# small_line.net
KiCad netlist of a schematic drawn in EAGLE
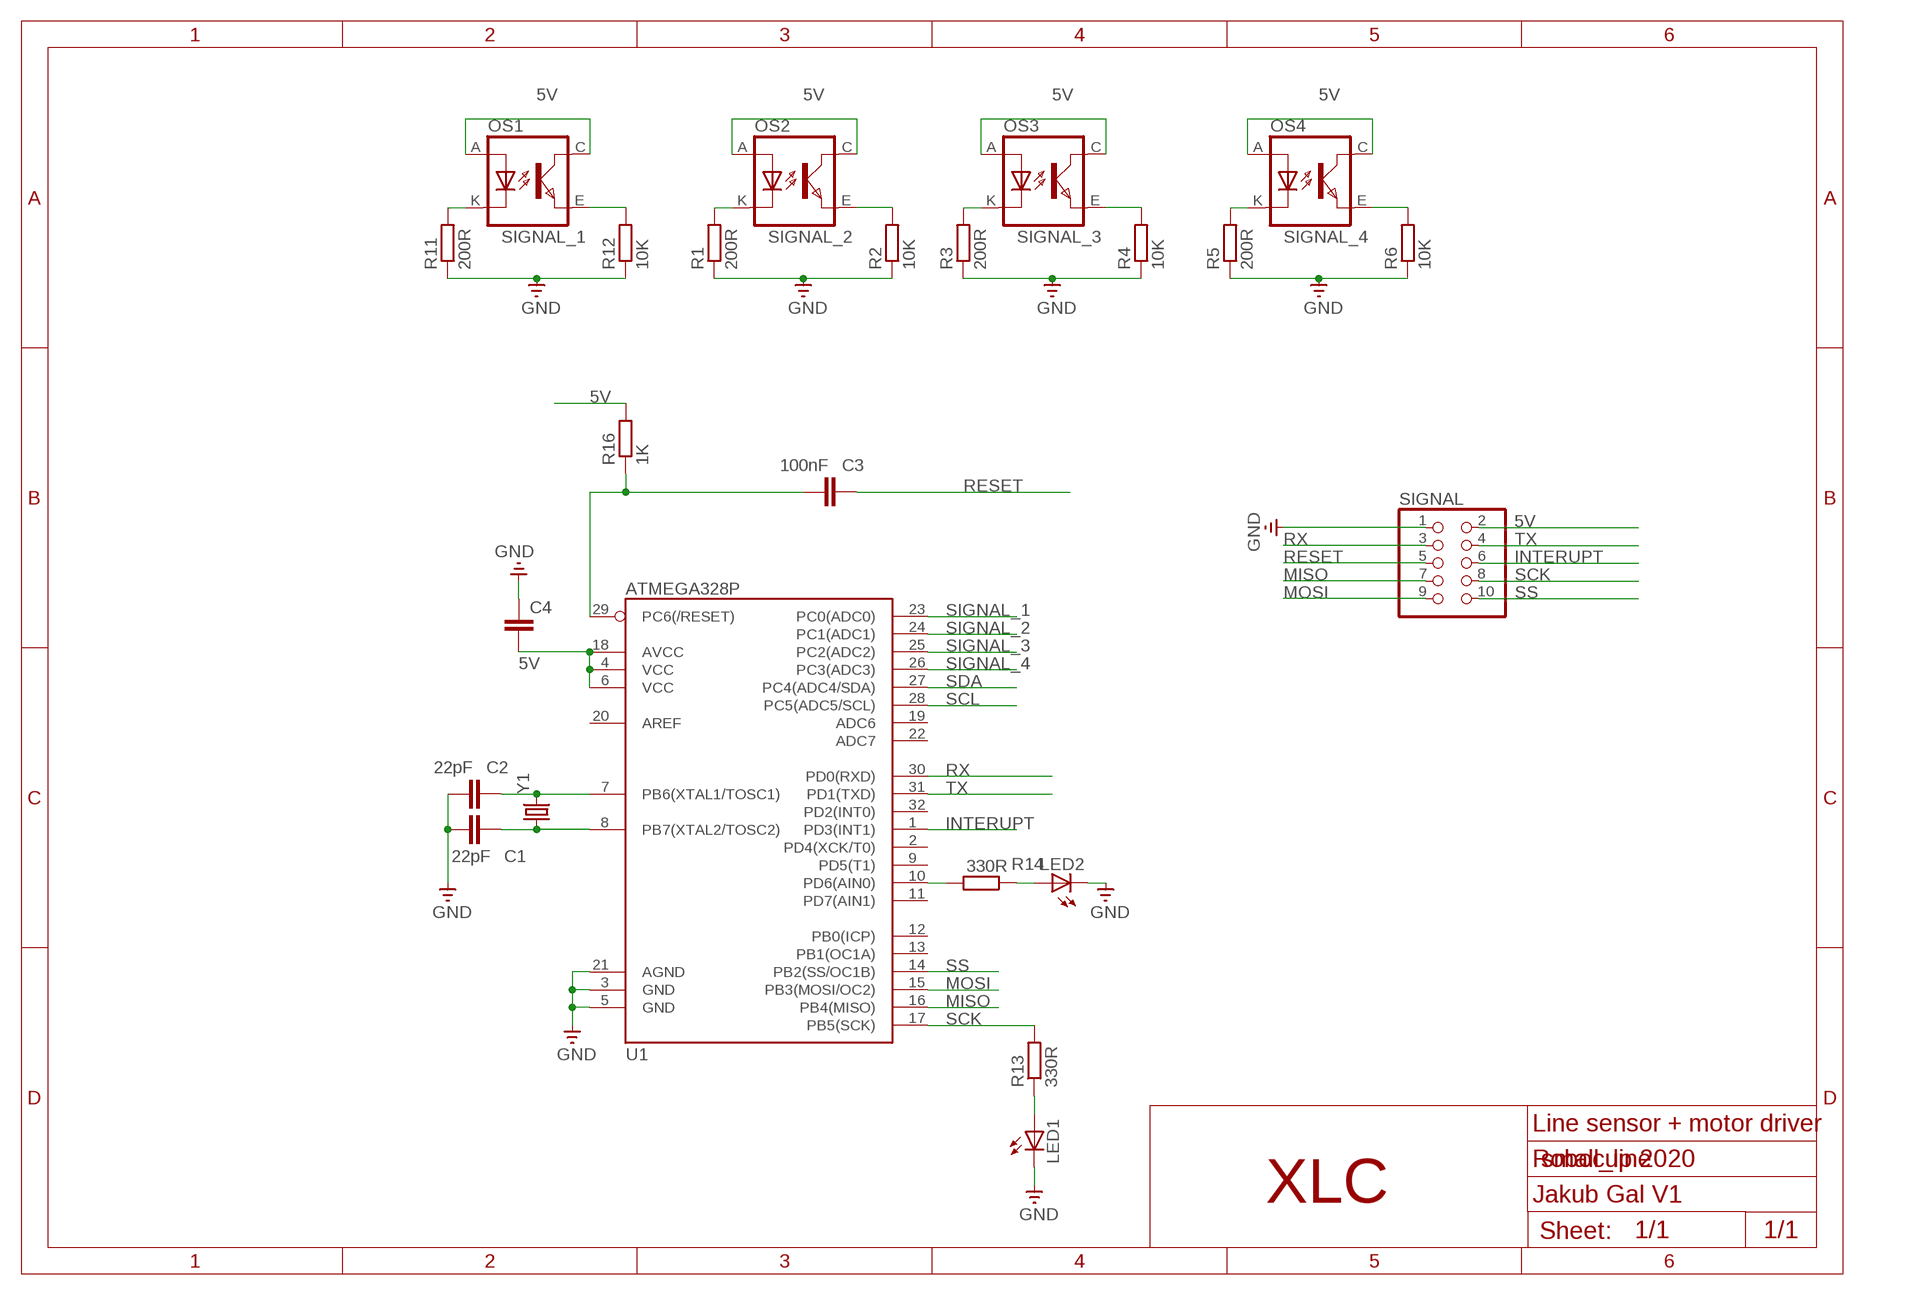
[diagram p0: schematic, sheet 1]

(export (version "E")
  (design (tool "Eeschema 10.0.6"))
  (components
    (comp (ref "C1")
      (value "22pF")
      (footprint "eagle-import:C0603")
      (libsource (lib "eagle-import") (part "C-EUC0603"))
    )
    (comp (ref "C2")
      (value "22pF")
      (footprint "eagle-import:C0603")
      (libsource (lib "eagle-import") (part "C-EUC0603"))
    )
    (comp (ref "C3")
      (value "100nF")
      (footprint "eagle-import:C0603")
      (libsource (lib "eagle-import") (part "C-EUC0603"))
    )
    (comp (ref "C4")
      (value "C-EUC0603")
      (footprint "eagle-import:C0603")
      (libsource (lib "eagle-import") (part "rcl_334_C-EUC0603"))
    )
    (comp (ref "LED1")
      (value "LEDCHIPLED_0603")
      (footprint "eagle-import:CHIPLED_0603")
      (libsource (lib "eagle-import") (part "LEDCHIPLED_0603"))
    )
    (comp (ref "LED2")
      (value "LEDCHIPLED_0603")
      (footprint "eagle-import:CHIPLED_0603")
      (libsource (lib "eagle-import") (part "LEDCHIPLED_0603"))
    )
    (comp (ref "OS1")
      (value "TCRT5000")
      (footprint "eagle-import:TCRT5000")
      (libsource (lib "eagle-import") (part "TCRT5000"))
    )
    (comp (ref "OS2")
      (value "TCRT5000")
      (footprint "eagle-import:TCRT5000")
      (libsource (lib "eagle-import") (part "TCRT5000"))
    )
    (comp (ref "OS3")
      (value "TCRT5000")
      (footprint "eagle-import:TCRT5000")
      (libsource (lib "eagle-import") (part "TCRT5000"))
    )
    (comp (ref "OS4")
      (value "TCRT5000")
      (footprint "eagle-import:TCRT5000")
      (libsource (lib "eagle-import") (part "TCRT5000"))
    )
    (comp (ref "R1")
      (value "200R")
      (footprint "eagle-import:R0603")
      (libsource (lib "eagle-import") (part "R-EU_R0603"))
    )
    (comp (ref "R2")
      (value "10K")
      (footprint "eagle-import:R0603")
      (libsource (lib "eagle-import") (part "R-EU_R0603"))
    )
    (comp (ref "R3")
      (value "200R")
      (footprint "eagle-import:R0603")
      (libsource (lib "eagle-import") (part "R-EU_R0603"))
    )
    (comp (ref "R4")
      (value "10K")
      (footprint "eagle-import:R0603")
      (libsource (lib "eagle-import") (part "R-EU_R0603"))
    )
    (comp (ref "R5")
      (value "200R")
      (footprint "eagle-import:R0603")
      (libsource (lib "eagle-import") (part "R-EU_R0603"))
    )
    (comp (ref "R6")
      (value "10K")
      (footprint "eagle-import:R0603")
      (libsource (lib "eagle-import") (part "R-EU_R0603"))
    )
    (comp (ref "R11")
      (value "200R")
      (footprint "eagle-import:R0603")
      (libsource (lib "eagle-import") (part "R-EU_R0603"))
    )
    (comp (ref "R12")
      (value "10K")
      (footprint "eagle-import:R0603")
      (libsource (lib "eagle-import") (part "R-EU_R0603"))
    )
    (comp (ref "R13")
      (value "330R")
      (footprint "eagle-import:R0603")
      (libsource (lib "eagle-import") (part "R-EU_R0603"))
    )
    (comp (ref "R14")
      (value "330R")
      (footprint "eagle-import:R0603")
      (libsource (lib "eagle-import") (part "R-EU_R0603"))
    )
    (comp (ref "R16")
      (value "1K")
      (footprint "eagle-import:R0603")
      (libsource (lib "eagle-import") (part "R-EU_R0603"))
    )
    (comp (ref "SIGNAL")
      (value "PINHD-2X5IDC")
      (footprint "eagle-import:2X05_IDC")
      (libsource (lib "eagle-import") (part "PINHD-2X5IDC"))
    )
    (comp (ref "U1")
      (value "ATMEGA328P")
      (footprint "eagle-import:TQFP32-08")
      (libsource (lib "eagle-import") (part "ATMEGA328_SMT"))
    )
    (comp (ref "Y1")
      (value "CRYSTALHC49US")
      (footprint "eagle-import:HC49US")
      (libsource (lib "eagle-import") (part "CRYSTALHC49US"))
    )
  )
  (nets
    (net (code "1") (name "/5V") (class "Default")
      (node (ref "C4") (pin "2") (pinfunction "2_2") (pintype "passive"))
      (node (ref "OS1") (pin "A") (pinfunction "ANODE_A") (pintype "passive"))
      (node (ref "OS1") (pin "C") (pinfunction "COLLECTOR_C") (pintype "passive"))
      (node (ref "OS2") (pin "A") (pinfunction "ANODE_A") (pintype "passive"))
      (node (ref "OS2") (pin "C") (pinfunction "COLLECTOR_C") (pintype "passive"))
      (node (ref "OS3") (pin "A") (pinfunction "ANODE_A") (pintype "passive"))
      (node (ref "OS3") (pin "C") (pinfunction "COLLECTOR_C") (pintype "passive"))
      (node (ref "OS4") (pin "A") (pinfunction "ANODE_A") (pintype "passive"))
      (node (ref "OS4") (pin "C") (pinfunction "COLLECTOR_C") (pintype "passive"))
      (node (ref "R16") (pin "2") (pinfunction "2_2") (pintype "passive"))
      (node (ref "SIGNAL") (pin "2") (pinfunction "2_2") (pintype "passive"))
      (node (ref "U1") (pin "18") (pinfunction "AVCC_18") (pintype "bidirectional"))
      (node (ref "U1") (pin "4") (pinfunction "VCC_4") (pintype "bidirectional"))
      (node (ref "U1") (pin "6") (pinfunction "VCC_6") (pintype "bidirectional"))
    )
    (net (code "2") (name "/INTERUPT") (class "Default")
      (node (ref "SIGNAL") (pin "6") (pinfunction "6_6") (pintype "passive"))
      (node (ref "U1") (pin "1") (pinfunction "PD3(INT1)_1") (pintype "bidirectional"))
    )
    (net (code "3") (name "/MISO") (class "Default")
      (node (ref "SIGNAL") (pin "7") (pinfunction "7_7") (pintype "passive"))
      (node (ref "U1") (pin "16") (pinfunction "PB4(MISO)_16") (pintype "bidirectional"))
    )
    (net (code "4") (name "/MOSI") (class "Default")
      (node (ref "SIGNAL") (pin "9") (pinfunction "9_9") (pintype "passive"))
      (node (ref "U1") (pin "15") (pinfunction "PB3(MOSI/OC2)_15") (pintype "bidirectional"))
    )
    (net (code "5") (name "/RESET") (class "Default")
      (node (ref "C3") (pin "2") (pinfunction "2_2") (pintype "passive"))
      (node (ref "SIGNAL") (pin "5") (pinfunction "5_5") (pintype "passive"))
    )
    (net (code "6") (name "/RX") (class "Default")
      (node (ref "SIGNAL") (pin "3") (pinfunction "3_3") (pintype "passive"))
      (node (ref "U1") (pin "30") (pinfunction "PD0(RXD)_30") (pintype "bidirectional"))
    )
    (net (code "7") (name "/SCK") (class "Default")
      (node (ref "R13") (pin "2") (pinfunction "2_2") (pintype "passive"))
      (node (ref "SIGNAL") (pin "8") (pinfunction "8_8") (pintype "passive"))
      (node (ref "U1") (pin "17") (pinfunction "PB5(SCK)_17") (pintype "bidirectional"))
    )
    (net (code "8") (name "/SCL") (class "Default")
      (node (ref "U1") (pin "28") (pinfunction "PC5(ADC5/SCL)_28") (pintype "bidirectional"))
    )
    (net (code "9") (name "/SDA") (class "Default")
      (node (ref "U1") (pin "27") (pinfunction "PC4(ADC4/SDA)_27") (pintype "bidirectional"))
    )
    (net (code "10") (name "/SIGNAL_1") (class "Default")
      (node (ref "OS1") (pin "E") (pinfunction "EMITTER_E") (pintype "passive"))
      (node (ref "R12") (pin "2") (pinfunction "2_2") (pintype "passive"))
      (node (ref "U1") (pin "23") (pinfunction "PC0(ADC0)_23") (pintype "bidirectional"))
    )
    (net (code "11") (name "/SIGNAL_2") (class "Default")
      (node (ref "OS2") (pin "E") (pinfunction "EMITTER_E") (pintype "passive"))
      (node (ref "R2") (pin "2") (pinfunction "2_2") (pintype "passive"))
      (node (ref "U1") (pin "24") (pinfunction "PC1(ADC1)_24") (pintype "bidirectional"))
    )
    (net (code "12") (name "/SIGNAL_3") (class "Default")
      (node (ref "OS3") (pin "E") (pinfunction "EMITTER_E") (pintype "passive"))
      (node (ref "R4") (pin "2") (pinfunction "2_2") (pintype "passive"))
      (node (ref "U1") (pin "25") (pinfunction "PC2(ADC2)_25") (pintype "bidirectional"))
    )
    (net (code "13") (name "/SIGNAL_4") (class "Default")
      (node (ref "OS4") (pin "E") (pinfunction "EMITTER_E") (pintype "passive"))
      (node (ref "R6") (pin "2") (pinfunction "2_2") (pintype "passive"))
      (node (ref "U1") (pin "26") (pinfunction "PC3(ADC3)_26") (pintype "bidirectional"))
    )
    (net (code "14") (name "/SS") (class "Default")
      (node (ref "SIGNAL") (pin "10") (pinfunction "10_10") (pintype "passive"))
      (node (ref "U1") (pin "14") (pinfunction "PB2(SS/OC1B)_14") (pintype "bidirectional"))
    )
    (net (code "15") (name "/TX") (class "Default")
      (node (ref "SIGNAL") (pin "4") (pinfunction "4_4") (pintype "passive"))
      (node (ref "U1") (pin "31") (pinfunction "PD1(TXD)_31") (pintype "bidirectional"))
    )
    (net (code "16") (name "GND") (class "Default")
      (node (ref "C1") (pin "1") (pinfunction "1_1") (pintype "passive"))
      (node (ref "C2") (pin "1") (pinfunction "1_1") (pintype "passive"))
      (node (ref "C4") (pin "1") (pinfunction "1_1") (pintype "passive"))
      (node (ref "LED1") (pin "C") (pinfunction "C_C") (pintype "passive"))
      (node (ref "LED2") (pin "C") (pinfunction "C_C") (pintype "passive"))
      (node (ref "R1") (pin "1") (pinfunction "1_1") (pintype "passive"))
      (node (ref "R11") (pin "1") (pinfunction "1_1") (pintype "passive"))
      (node (ref "R12") (pin "1") (pinfunction "1_1") (pintype "passive"))
      (node (ref "R2") (pin "1") (pinfunction "1_1") (pintype "passive"))
      (node (ref "R3") (pin "1") (pinfunction "1_1") (pintype "passive"))
      (node (ref "R4") (pin "1") (pinfunction "1_1") (pintype "passive"))
      (node (ref "R5") (pin "1") (pinfunction "1_1") (pintype "passive"))
      (node (ref "R6") (pin "1") (pinfunction "1_1") (pintype "passive"))
      (node (ref "SIGNAL") (pin "1") (pinfunction "1_1") (pintype "passive"))
      (node (ref "U1") (pin "21") (pinfunction "AGND_21") (pintype "bidirectional"))
      (node (ref "U1") (pin "3") (pinfunction "GND_3") (pintype "bidirectional"))
      (node (ref "U1") (pin "5") (pinfunction "GND_5") (pintype "bidirectional"))
    )
    (net (code "17") (name "Net-(LED1-PadA)") (class "Default")
      (node (ref "LED1") (pin "A") (pinfunction "A_A") (pintype "passive"))
      (node (ref "R13") (pin "1") (pinfunction "1_1") (pintype "passive"))
    )
    (net (code "18") (name "Net-(LED2-PadA)") (class "Default")
      (node (ref "LED2") (pin "A") (pinfunction "A_A") (pintype "passive"))
      (node (ref "R14") (pin "1") (pinfunction "1_1") (pintype "passive"))
    )
    (net (code "19") (name "Net-(OS1-CATHODE)") (class "Default")
      (node (ref "OS1") (pin "K") (pinfunction "CATHODE_K") (pintype "passive"))
      (node (ref "R11") (pin "2") (pinfunction "2_2") (pintype "passive"))
    )
    (net (code "20") (name "Net-(OS2-CATHODE)") (class "Default")
      (node (ref "OS2") (pin "K") (pinfunction "CATHODE_K") (pintype "passive"))
      (node (ref "R1") (pin "2") (pinfunction "2_2") (pintype "passive"))
    )
    (net (code "21") (name "Net-(OS3-CATHODE)") (class "Default")
      (node (ref "OS3") (pin "K") (pinfunction "CATHODE_K") (pintype "passive"))
      (node (ref "R3") (pin "2") (pinfunction "2_2") (pintype "passive"))
    )
    (net (code "22") (name "Net-(OS4-CATHODE)") (class "Default")
      (node (ref "OS4") (pin "K") (pinfunction "CATHODE_K") (pintype "passive"))
      (node (ref "R5") (pin "2") (pinfunction "2_2") (pintype "passive"))
    )
    (net (code "23") (name "Net-(U1-PB6(XTAL1{slash}TOSC1))") (class "Default")
      (node (ref "C2") (pin "2") (pinfunction "2_2") (pintype "passive"))
      (node (ref "U1") (pin "7") (pinfunction "PB6(XTAL1/TOSC1)_7") (pintype "bidirectional"))
      (node (ref "Y1") (pin "2") (pinfunction "2_2") (pintype "passive"))
    )
    (net (code "24") (name "Net-(U1-PB7(XTAL2{slash}TOSC2))") (class "Default")
      (node (ref "C1") (pin "2") (pinfunction "2_2") (pintype "passive"))
      (node (ref "U1") (pin "8") (pinfunction "PB7(XTAL2/TOSC2)_8") (pintype "bidirectional"))
      (node (ref "Y1") (pin "1") (pinfunction "1_1") (pintype "passive"))
    )
    (net (code "25") (name "Net-(U1-PC6({slash}RESET))") (class "Default")
      (node (ref "C3") (pin "1") (pinfunction "1_1") (pintype "passive"))
      (node (ref "R16") (pin "1") (pinfunction "1_1") (pintype "passive"))
      (node (ref "U1") (pin "29") (pinfunction "PC6(/RESET)_29") (pintype "bidirectional"))
    )
    (net (code "26") (name "Net-(U1-PD6(AIN0))") (class "Default")
      (node (ref "R14") (pin "2") (pinfunction "2_2") (pintype "passive"))
      (node (ref "U1") (pin "10") (pinfunction "PD6(AIN0)_10") (pintype "bidirectional"))
    )
    (net (code "27") (name "unconnected-(U1-ADC6-Pad19)") (class "Default")
      (node (ref "U1") (pin "19") (pinfunction "ADC6_19") (pintype "bidirectional"))
    )
    (net (code "28") (name "unconnected-(U1-ADC7-Pad22)") (class "Default")
      (node (ref "U1") (pin "22") (pinfunction "ADC7_22") (pintype "bidirectional"))
    )
    (net (code "29") (name "unconnected-(U1-AREF-Pad20)") (class "Default")
      (node (ref "U1") (pin "20") (pinfunction "AREF_20") (pintype "bidirectional"))
    )
    (net (code "30") (name "unconnected-(U1-PB0(ICP)-Pad12)") (class "Default")
      (node (ref "U1") (pin "12") (pinfunction "PB0(ICP)_12") (pintype "bidirectional"))
    )
    (net (code "31") (name "unconnected-(U1-PB1(OC1A)-Pad13)") (class "Default")
      (node (ref "U1") (pin "13") (pinfunction "PB1(OC1A)_13") (pintype "bidirectional"))
    )
    (net (code "32") (name "unconnected-(U1-PD2(INT0)-Pad32)") (class "Default")
      (node (ref "U1") (pin "32") (pinfunction "PD2(INT0)_32") (pintype "bidirectional"))
    )
    (net (code "33") (name "unconnected-(U1-PD4(XCK{slash}T0)-Pad2)") (class "Default")
      (node (ref "U1") (pin "2") (pinfunction "PD4(XCK/T0)_2") (pintype "bidirectional"))
    )
    (net (code "34") (name "unconnected-(U1-PD5(T1)-Pad9)") (class "Default")
      (node (ref "U1") (pin "9") (pinfunction "PD5(T1)_9") (pintype "bidirectional"))
    )
    (net (code "35") (name "unconnected-(U1-PD7(AIN1)-Pad11)") (class "Default")
      (node (ref "U1") (pin "11") (pinfunction "PD7(AIN1)_11") (pintype "bidirectional"))
    )
  )
)
